# Sheet_1.net
KiCad netlist of a schematic drawn in Altium Designer
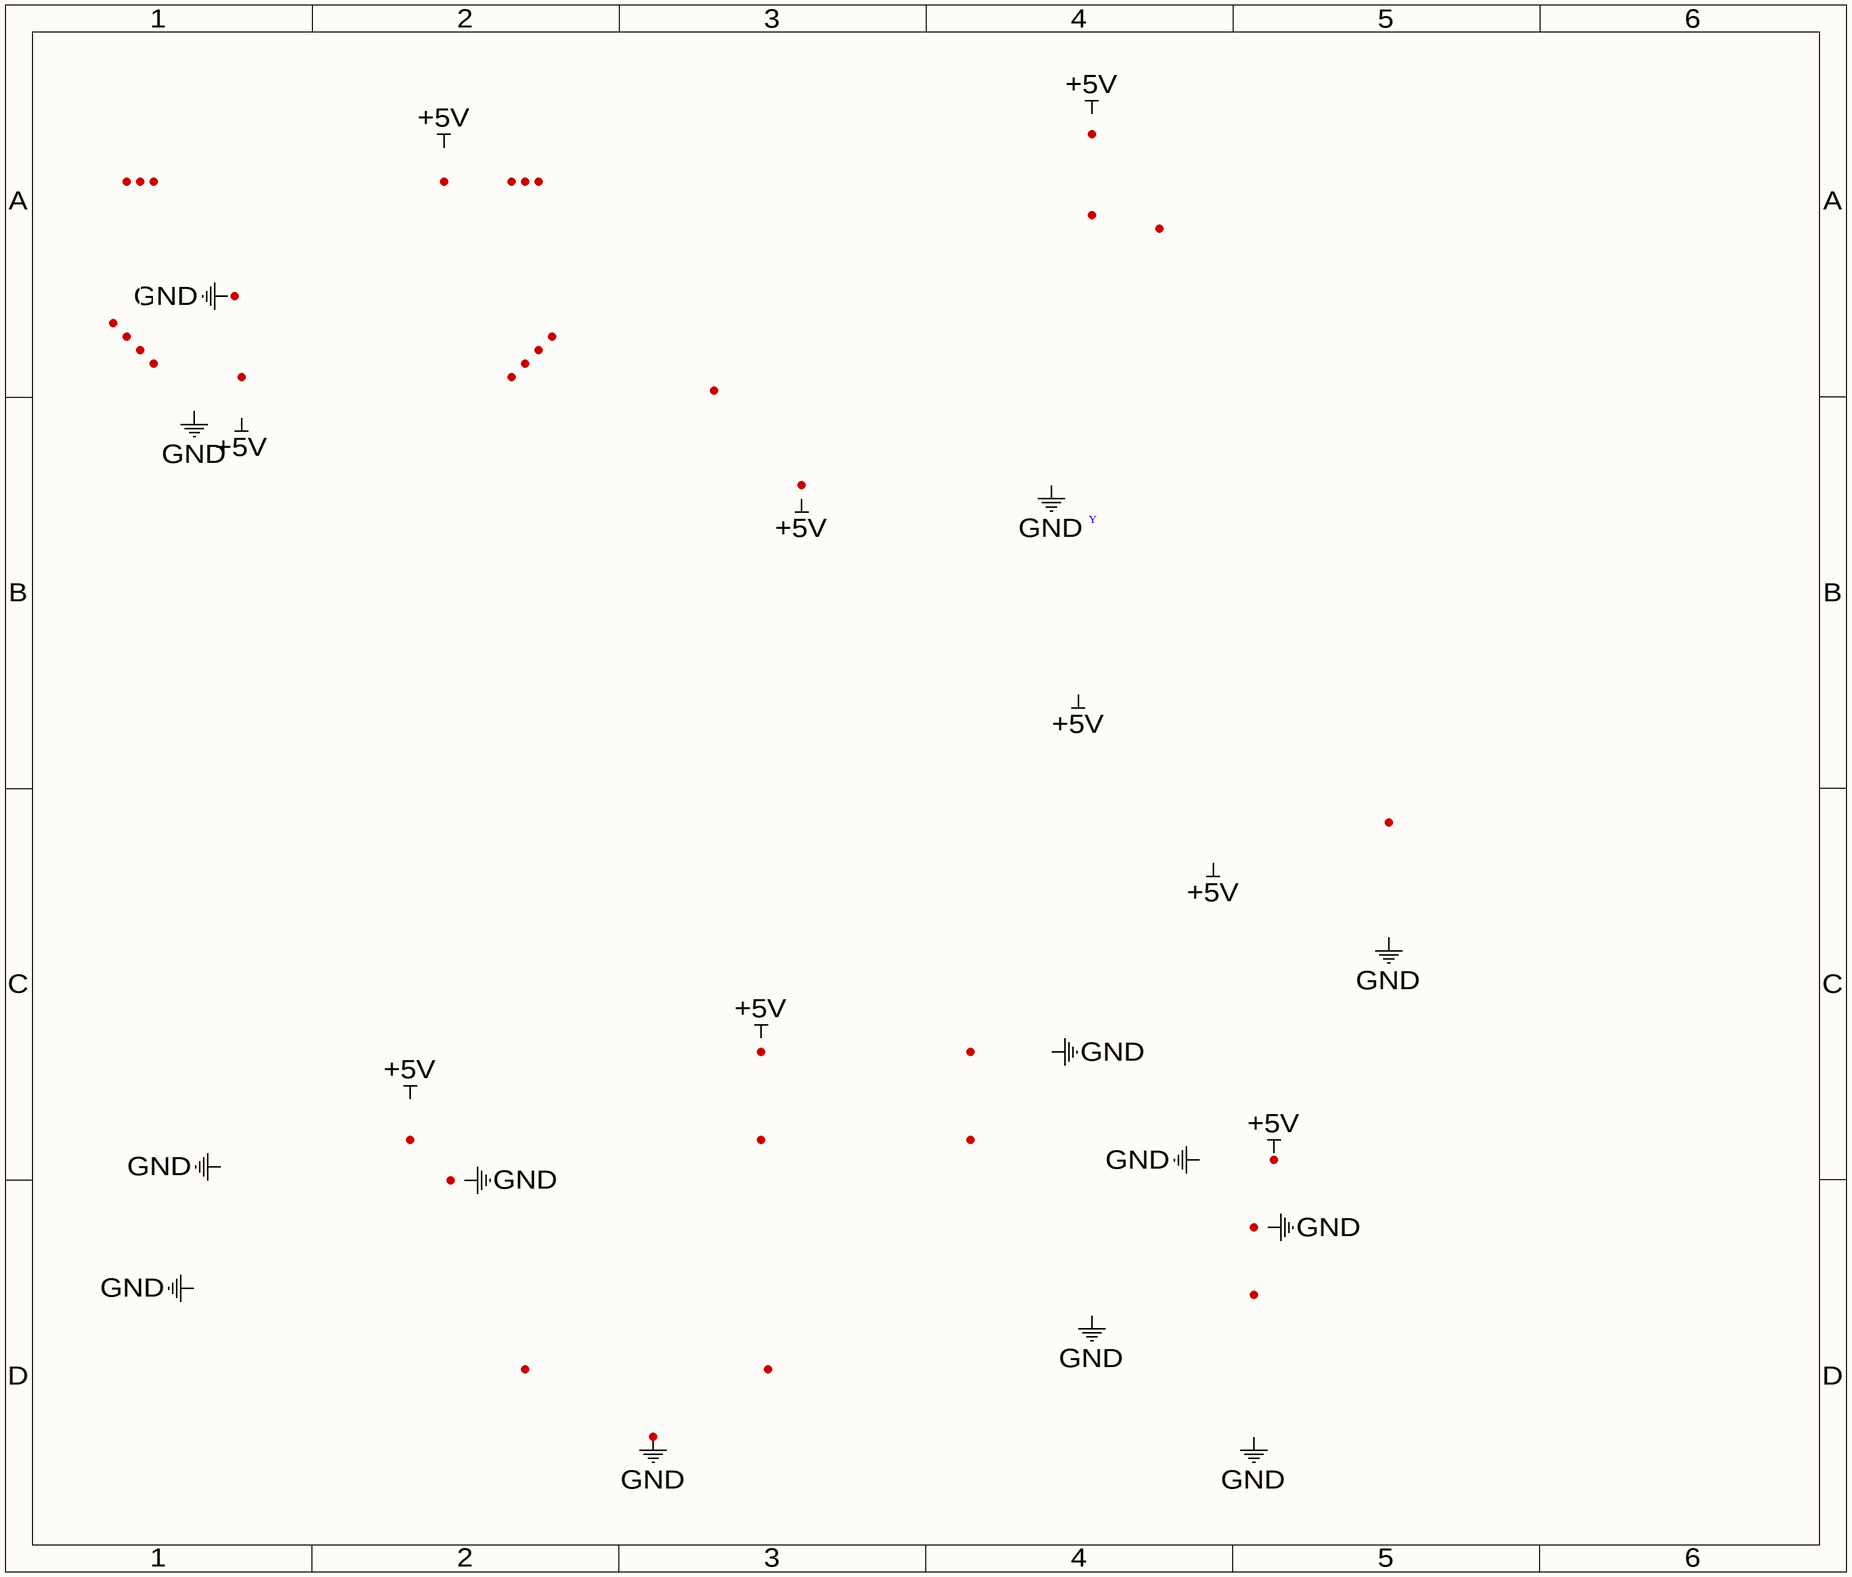
[diagram p0: Sheet_1.schdoc]

(export (version "E")
  (design (tool "Eeschema 10.0.6"))
  (components
    (comp (ref "BOARD1")
      (value "ESP32DEVKITV1")
      (fields (field (name "CONTRIBUTOR") "radio"))
      (libsource (lib "altium-import") (part "root_0_ESP32DEVKITV1_"))
    )
    (comp (ref "C1")
      (value "100nF")
      (fields
        (field (name "BOM_SUPPLIER PART") "C328914")
        (field (name "BOM_MANUFACTURER PART") "FN15X104K160PNG")
        (field (name "CONTRIBUTOR") "LCSC")
      )
      (libsource (lib "altium-import") (part "root_2_100nF_"))
    )
    (comp (ref "C2")
      (value "100nF")
      (fields
        (field (name "BOM_SUPPLIER PART") "C328914")
        (field (name "BOM_MANUFACTURER PART") "FN15X104K160PNG")
        (field (name "CONTRIBUTOR") "LCSC")
      )
      (libsource (lib "altium-import") (part "root_2_100nF_"))
    )
    (comp (ref "C3")
      (value "100nF")
      (fields
        (field (name "BOM_SUPPLIER PART") "C328914")
        (field (name "BOM_MANUFACTURER PART") "FN15X104K160PNG")
        (field (name "CONTRIBUTOR") "LCSC")
      )
      (libsource (lib "altium-import") (part "root_1_100nF_"))
    )
    (comp (ref "C4")
      (value "100nF")
      (fields
        (field (name "BOM_SUPPLIER PART") "C328914")
        (field (name "BOM_MANUFACTURER PART") "FN15X104K160PNG")
        (field (name "CONTRIBUTOR") "LCSC")
      )
      (libsource (lib "altium-import") (part "root_3_100nF_"))
    )
    (comp (ref "C5")
      (value "100nF")
      (fields
        (field (name "BOM_SUPPLIER PART") "C328914")
        (field (name "BOM_MANUFACTURER PART") "FN15X104K160PNG")
        (field (name "CONTRIBUTOR") "LCSC")
      )
      (libsource (lib "altium-import") (part "root_2_100nF_"))
    )
    (comp (ref "C6")
      (value "100nF")
      (fields
        (field (name "BOM_SUPPLIER PART") "C328914")
        (field (name "BOM_MANUFACTURER PART") "FN15X104K160PNG")
        (field (name "CONTRIBUTOR") "LCSC")
      )
      (libsource (lib "altium-import") (part "root_2_100nF_"))
    )
    (comp (ref "D1")
      (value "SS34")
      (fields (field (name "BOM_SUPPLIER PART") "C83961"))
      (libsource (lib "altium-import") (part "root_3_SS34_"))
    )
    (comp (ref "D2")
      (value "SS34")
      (fields (field (name "BOM_SUPPLIER PART") "C83961"))
      (libsource (lib "altium-import") (part "root_3_SS34_"))
    )
    (comp (ref "ERROR")
      (value "17-21SURC/S530-A2/TR8")
      (fields (field (name "BOM_SUPPLIER PART") "C131244") (field (name "CONTRIBUTOR") "LCSC"))
      (libsource (lib "altium-import") (part "root_1_17-21SURC/S530-A2/TR8_"))
    )
    (comp (ref "GC")
      (value "17-21SURC/S530-A2/TR8")
      (fields (field (name "BOM_SUPPLIER PART") "C131244") (field (name "CONTRIBUTOR") "LCSC"))
      (libsource (lib "altium-import") (part "root_1_17-21SURC/S530-A2/TR8_"))
    )
    (comp (ref "GL")
      (value "17-21SURC/S530-A2/TR8")
      (fields (field (name "BOM_SUPPLIER PART") "C131244") (field (name "CONTRIBUTOR") "LCSC"))
      (libsource (lib "altium-import") (part "root_1_17-21SURC/S530-A2/TR8_"))
    )
    (comp (ref "GR")
      (value "17-21SURC/S530-A2/TR8")
      (fields (field (name "BOM_SUPPLIER PART") "C131244") (field (name "CONTRIBUTOR") "LCSC"))
      (libsource (lib "altium-import") (part "root_1_17-21SURC/S530-A2/TR8_"))
    )
    (comp (ref "K1")
      (value "KH-3635-CAJ")
      (fields (field (name "BOM_SUPPLIER PART") "C530670") (field (name "CONTRIBUTOR") "LCSC"))
      (libsource (lib "altium-import") (part "root_0_KH-3635-CAJ_"))
    )
    (comp (ref "K2")
      (value "KH-3635-CAJ")
      (fields (field (name "BOM_SUPPLIER PART") "C530670") (field (name "CONTRIBUTOR") "LCSC"))
      (libsource (lib "altium-import") (part "root_0_KH-3635-CAJ_"))
    )
    (comp (ref "OLED1")
      (value "0.96OLED_4P")
      (fields (field (name "CONTRIBUTOR") "LCEDA_Lib"))
      (libsource (lib "altium-import") (part "root_0_0.96OLED_4P_"))
    )
    (comp (ref "OPEN")
      (value "SK-3296S-01-L1")
      (fields (field (name "BOM_SUPPLIER PART") "C319020") (field (name "CONTRIBUTOR") "LCSC"))
      (libsource (lib "altium-import") (part "root_1_SK-3296S-01-L1_"))
    )
    (comp (ref "POWER")
      (value "17-21SYGC/S530-E3/TR8")
      (fields (field (name "BOM_SUPPLIER PART") "C142303") (field (name "CONTRIBUTOR") "LCSC"))
      (libsource (lib "altium-import") (part "root_1_17-21SYGC/S530-E3/TR8_"))
    )
    (comp (ref "R1")
      (value "510")
      (fields
        (field (name "BOM_MANUFACTURER PART") "0603WAF1002T5E")
        (field (name "BOM_SUPPLIER PART") "C25804")
      )
      (libsource (lib "altium-import") (part "root_1_510_"))
    )
    (comp (ref "R2")
      (value "1k")
      (fields
        (field (name "BOM_MANUFACTURER PART") "0603WAF1002T5E")
        (field (name "BOM_SUPPLIER PART") "C25804")
      )
      (libsource (lib "altium-import") (part "root_1_1k_"))
    )
    (comp (ref "R3")
      (value "1k")
      (fields
        (field (name "BOM_MANUFACTURER PART") "0603WAF1002T5E")
        (field (name "BOM_SUPPLIER PART") "C25804")
      )
      (libsource (lib "altium-import") (part "root_1_1k_"))
    )
    (comp (ref "R4")
      (value "4.7k")
      (fields
        (field (name "BOM_MANUFACTURER PART") "0603WAF1002T5E")
        (field (name "BOM_SUPPLIER PART") "C25804")
      )
      (libsource (lib "altium-import") (part "root_1_4.7k_"))
    )
    (comp (ref "R5")
      (value "4.7k")
      (fields
        (field (name "BOM_MANUFACTURER PART") "0603WAF1002T5E")
        (field (name "BOM_SUPPLIER PART") "C25804")
      )
      (libsource (lib "altium-import") (part "root_1_4.7k_"))
    )
    (comp (ref "RC")
      (value "17-21SURC/S530-A2/TR8")
      (fields (field (name "BOM_SUPPLIER PART") "C131244") (field (name "CONTRIBUTOR") "LCSC"))
      (libsource (lib "altium-import") (part "root_1_17-21SURC/S530-A2/TR8_"))
    )
    (comp (ref "RL")
      (value "17-21SURC/S530-A2/TR8")
      (fields (field (name "BOM_SUPPLIER PART") "C131244") (field (name "CONTRIBUTOR") "LCSC"))
      (libsource (lib "altium-import") (part "root_1_17-21SURC/S530-A2/TR8_"))
    )
    (comp (ref "RN1")
      (value "1k")
      (fields
        (field (name "BOM_MANUFACTURER PART") "YC164-FR-071KL")
        (field (name "BOM_SUPPLIER PART") "C110021")
      )
      (libsource (lib "altium-import") (part "root_0_1k_"))
    )
    (comp (ref "RN2")
      (value "1k")
      (fields
        (field (name "BOM_MANUFACTURER PART") "YC164-FR-071KL")
        (field (name "BOM_SUPPLIER PART") "C110021")
      )
      (libsource (lib "altium-import") (part "root_0_1k_"))
    )
    (comp (ref "RN3")
      (value "1k")
      (fields
        (field (name "BOM_MANUFACTURER PART") "YC164-FR-071KL")
        (field (name "BOM_SUPPLIER PART") "C110021")
      )
      (libsource (lib "altium-import") (part "root_0_1k_"))
    )
    (comp (ref "RN4")
      (value "1k")
      (fields
        (field (name "BOM_MANUFACTURER PART") "YC164-FR-071KL")
        (field (name "BOM_SUPPLIER PART") "C110021")
      )
      (libsource (lib "altium-import") (part "root_0_1k_"))
    )
    (comp (ref "RR")
      (value "17-21SURC/S530-A2/TR8")
      (fields (field (name "BOM_SUPPLIER PART") "C131244") (field (name "CONTRIBUTOR") "LCSC"))
      (libsource (lib "altium-import") (part "root_1_17-21SURC/S530-A2/TR8_"))
    )
    (comp (ref "U1")
      (value "PCF8574T/3,518")
      (fields (field (name "BOM_SUPPLIER PART") "C7605"))
      (libsource (lib "altium-import") (part "root_0_PCF8574T/3,518_"))
    )
    (comp (ref "U2")
      (value "74HC240D,653")
      (fields (field (name "BOM_SUPPLIER PART") "C8094"))
      (libsource (lib "altium-import") (part "root_0_74HC240D,653_"))
    )
    (comp (ref "U3")
      (value "74HC30D,653")
      (fields (field (name "BOM_SUPPLIER PART") "C5631"))
      (libsource (lib "altium-import") (part "root_0_74HC30D,653_"))
    )
    (comp (ref "U4")
      (value "74HC30D,653")
      (fields (field (name "BOM_SUPPLIER PART") "C5631"))
      (libsource (lib "altium-import") (part "root_0_74HC30D,653_"))
    )
    (comp (ref "U5")
      (value "AMS1117-3.3_C347222")
      (fields
        (field (name "BOM_SUPPLIER PART") "C347222")
        (field (name "BOM_MANUFACTURER PART") "AMS1117-3.3")
        (field (name "CONTRIBUTOR") "LCSC")
      )
      (libsource (lib "altium-import") (part "root_0_AMS1117-3.3_C347222_"))
    )
    (comp (ref "U6")
      (value "74HC30D,653")
      (fields (field (name "BOM_SUPPLIER PART") "C5631"))
      (libsource (lib "altium-import") (part "root_0_74HC30D,653_"))
    )
    (comp (ref "U7")
      (value "74HC30D,653")
      (fields (field (name "BOM_SUPPLIER PART") "C5631"))
      (libsource (lib "altium-import") (part "root_0_74HC30D,653_"))
    )
    (comp (ref "U8")
      (value "74HC08D,653")
      (fields (field (name "BOM_SUPPLIER PART") "C5593"))
      (libsource (lib "altium-import") (part "root_0_74HC08D,653_"))
    )
    (comp (ref "USB1")
      (value "KH-TYPE-C-6P")
      (fields (field (name "BOM_SUPPLIER PART") "C709355") (field (name "CONTRIBUTOR") "LCSC"))
      (libsource (lib "altium-import") (part "root_0_KH-TYPE-C-6P_"))
    )
    (comp (ref "YL")
      (value "17-21SURC/S530-A2/TR8")
      (fields (field (name "BOM_SUPPLIER PART") "C131244") (field (name "CONTRIBUTOR") "LCSC"))
      (libsource (lib "altium-import") (part "root_1_17-21SURC/S530-A2/TR8_"))
    )
    (comp (ref "YR")
      (value "17-21SURC/S530-A2/TR8")
      (fields (field (name "BOM_SUPPLIER PART") "C131244") (field (name "CONTRIBUTOR") "LCSC"))
      (libsource (lib "altium-import") (part "root_1_17-21SURC/S530-A2/TR8_"))
    )
  )
  (nets
    (net (code "1") (name "+5V") (class "Default")
      (node (ref "C1") (pin "2") (pinfunction "2_2") (pintype "passive"))
      (node (ref "C2") (pin "1") (pinfunction "1_1") (pintype "passive"))
      (node (ref "C4") (pin "2") (pinfunction "2_2") (pintype "passive"))
      (node (ref "C5") (pin "2") (pinfunction "2_2") (pintype "passive"))
      (node (ref "C6") (pin "1") (pinfunction "1_1") (pintype "passive"))
      (node (ref "D1") (pin "2") (pinfunction "A_2") (pintype "passive"))
      (node (ref "OPEN") (pin "1") (pinfunction "1_1") (pintype "passive"))
      (node (ref "R4") (pin "2") (pinfunction "2_2") (pintype "passive"))
      (node (ref "R5") (pin "2") (pinfunction "2_2") (pintype "passive"))
      (node (ref "RN3") (pin "5") (pinfunction "5_5") (pintype "passive"))
      (node (ref "RN3") (pin "6") (pinfunction "6_6") (pintype "passive"))
      (node (ref "RN3") (pin "7") (pinfunction "7_7") (pintype "passive"))
      (node (ref "RN3") (pin "8") (pinfunction "8_8") (pintype "passive"))
      (node (ref "RN4") (pin "5") (pinfunction "5_5") (pintype "passive"))
      (node (ref "RN4") (pin "6") (pinfunction "6_6") (pintype "passive"))
      (node (ref "RN4") (pin "7") (pinfunction "7_7") (pintype "passive"))
      (node (ref "RN4") (pin "8") (pinfunction "8_8") (pintype "passive"))
      (node (ref "U1") (pin "16") (pinfunction "VDD_16") (pintype "passive"))
      (node (ref "U2") (pin "20") (pinfunction "VCC_20") (pintype "passive"))
      (node (ref "U3") (pin "14") (pinfunction "VCC_14") (pintype "passive"))
      (node (ref "U4") (pin "14") (pinfunction "VCC_14") (pintype "passive"))
      (node (ref "U5") (pin "3") (pinfunction "VIN_3") (pintype "passive"))
      (node (ref "U6") (pin "14") (pinfunction "VCC_14") (pintype "passive"))
      (node (ref "U7") (pin "14") (pinfunction "VCC_14") (pintype "passive"))
      (node (ref "U8") (pin "14") (pinfunction "VCC_14") (pintype "passive"))
    )
    (net (code "2") (name "/+3.3V") (class "Default")
      (node (ref "C3") (pin "1") (pinfunction "1_1") (pintype "passive"))
      (node (ref "OLED1") (pin "2") (pinfunction "2_2") (pintype "passive"))
      (node (ref "R1") (pin "2") (pinfunction "2_2") (pintype "passive"))
      (node (ref "U5") (pin "2") (pinfunction "VOUT(TAB)_2") (pintype "passive"))
      (node (ref "U5") (pin "4") (pinfunction "TAB_4") (pintype "passive"))
    )
    (net (code "3") (name "/A") (class "Default")
      (node (ref "RN1") (pin "8") (pinfunction "8_8") (pintype "passive"))
      (node (ref "RN3") (pin "1") (pinfunction "1_1") (pintype "passive"))
      (node (ref "U1") (pin "4") (pinfunction "P0_4") (pintype "passive"))
      (node (ref "U2") (pin "2") (pinfunction "1A0_2") (pintype "passive"))
      (node (ref "U3") (pin "1") (pinfunction "A_1") (pintype "passive"))
    )
    (net (code "4") (name "/A`") (class "Default")
      (node (ref "U2") (pin "18") (pinfunction "1Y0_18") (pintype "passive"))
      (node (ref "U4") (pin "1") (pinfunction "A_1") (pintype "passive"))
      (node (ref "U6") (pin "1") (pinfunction "A_1") (pintype "passive"))
      (node (ref "U7") (pin "1") (pinfunction "A_1") (pintype "passive"))
    )
    (net (code "5") (name "/B") (class "Default")
      (node (ref "RN1") (pin "7") (pinfunction "7_7") (pintype "passive"))
      (node (ref "RN3") (pin "2") (pinfunction "2_2") (pintype "passive"))
      (node (ref "U1") (pin "5") (pinfunction "P1_5") (pintype "passive"))
      (node (ref "U2") (pin "4") (pinfunction "1A1_4") (pintype "passive"))
      (node (ref "U7") (pin "2") (pinfunction "B_2") (pintype "passive"))
    )
    (net (code "6") (name "/B`") (class "Default")
      (node (ref "U2") (pin "16") (pinfunction "1Y1_16") (pintype "passive"))
      (node (ref "U3") (pin "2") (pinfunction "B_2") (pintype "passive"))
      (node (ref "U4") (pin "2") (pinfunction "B_2") (pintype "passive"))
      (node (ref "U6") (pin "2") (pinfunction "B_2") (pintype "passive"))
    )
    (net (code "7") (name "/C") (class "Default")
      (node (ref "RN1") (pin "6") (pinfunction "6_6") (pintype "passive"))
      (node (ref "RN3") (pin "3") (pinfunction "3_3") (pintype "passive"))
      (node (ref "U1") (pin "6") (pinfunction "P2_6") (pintype "passive"))
      (node (ref "U2") (pin "6") (pinfunction "1A2_6") (pintype "passive"))
      (node (ref "U4") (pin "3") (pinfunction "C_3") (pintype "passive"))
      (node (ref "U6") (pin "3") (pinfunction "C_3") (pintype "passive"))
    )
    (net (code "8") (name "/C`") (class "Default")
      (node (ref "U2") (pin "14") (pinfunction "1Y2_14") (pintype "passive"))
      (node (ref "U3") (pin "3") (pinfunction "C_3") (pintype "passive"))
      (node (ref "U7") (pin "3") (pinfunction "C_3") (pintype "passive"))
    )
    (net (code "9") (name "/D") (class "Default")
      (node (ref "RN1") (pin "5") (pinfunction "5_5") (pintype "passive"))
      (node (ref "RN3") (pin "4") (pinfunction "4_4") (pintype "passive"))
      (node (ref "U1") (pin "7") (pinfunction "P3_7") (pintype "passive"))
      (node (ref "U2") (pin "8") (pinfunction "1A3_8") (pintype "passive"))
      (node (ref "U4") (pin "4") (pinfunction "D_4") (pintype "passive"))
      (node (ref "U6") (pin "4") (pinfunction "D_4") (pintype "passive"))
    )
    (net (code "10") (name "/DC") (class "Default")
      (node (ref "OPEN") (pin "2") (pinfunction "2_2") (pintype "passive"))
      (node (ref "USB1") (pin "A9") (pinfunction "VBUS_A9") (pintype "passive"))
      (node (ref "USB1") (pin "B9") (pinfunction "VBUS_B9") (pintype "passive"))
    )
    (net (code "11") (name "/D`") (class "Default")
      (node (ref "U2") (pin "12") (pinfunction "1Y3_12") (pintype "passive"))
      (node (ref "U3") (pin "4") (pinfunction "D_4") (pintype "passive"))
      (node (ref "U7") (pin "4") (pinfunction "D_4") (pintype "passive"))
    )
    (net (code "12") (name "/E") (class "Default")
      (node (ref "RN2") (pin "8") (pinfunction "8_8") (pintype "passive"))
      (node (ref "RN4") (pin "1") (pinfunction "1_1") (pintype "passive"))
      (node (ref "U1") (pin "9") (pinfunction "P4_9") (pintype "passive"))
      (node (ref "U2") (pin "17") (pinfunction "2A0_17") (pintype "passive"))
      (node (ref "U7") (pin "5") (pinfunction "E_5") (pintype "passive"))
    )
    (net (code "13") (name "/E`") (class "Default")
      (node (ref "U2") (pin "3") (pinfunction "2Y0_3") (pintype "passive"))
      (node (ref "U3") (pin "5") (pinfunction "E_5") (pintype "passive"))
      (node (ref "U4") (pin "5") (pinfunction "E_5") (pintype "passive"))
      (node (ref "U6") (pin "5") (pinfunction "E_5") (pintype "passive"))
    )
    (net (code "14") (name "/F") (class "Default")
      (node (ref "RN2") (pin "7") (pinfunction "7_7") (pintype "passive"))
      (node (ref "RN4") (pin "2") (pinfunction "2_2") (pintype "passive"))
      (node (ref "U1") (pin "10") (pinfunction "P5_10") (pintype "passive"))
      (node (ref "U2") (pin "15") (pinfunction "2A1_15") (pintype "passive"))
      (node (ref "U3") (pin "6") (pinfunction "F_6") (pintype "passive"))
    )
    (net (code "15") (name "/F`") (class "Default")
      (node (ref "U2") (pin "5") (pinfunction "2Y1_5") (pintype "passive"))
      (node (ref "U4") (pin "6") (pinfunction "F_6") (pintype "passive"))
      (node (ref "U6") (pin "6") (pinfunction "F_6") (pintype "passive"))
      (node (ref "U7") (pin "6") (pinfunction "F_6") (pintype "passive"))
    )
    (net (code "16") (name "/G") (class "Default")
      (node (ref "RN2") (pin "6") (pinfunction "6_6") (pintype "passive"))
      (node (ref "RN4") (pin "3") (pinfunction "3_3") (pintype "passive"))
      (node (ref "U1") (pin "11") (pinfunction "P6_11") (pintype "passive"))
      (node (ref "U2") (pin "13") (pinfunction "2A2_13") (pintype "passive"))
      (node (ref "U3") (pin "11") (pinfunction "G_11") (pintype "passive"))
      (node (ref "U4") (pin "11") (pinfunction "G_11") (pintype "passive"))
      (node (ref "U7") (pin "11") (pinfunction "G_11") (pintype "passive"))
    )
    (net (code "17") (name "/G`") (class "Default")
      (node (ref "U2") (pin "7") (pinfunction "2Y2_7") (pintype "passive"))
      (node (ref "U6") (pin "11") (pinfunction "G_11") (pintype "passive"))
    )
    (net (code "18") (name "/H") (class "Default")
      (node (ref "RN2") (pin "5") (pinfunction "5_5") (pintype "passive"))
      (node (ref "RN4") (pin "4") (pinfunction "4_4") (pintype "passive"))
      (node (ref "U1") (pin "12") (pinfunction "P7_12") (pintype "passive"))
      (node (ref "U2") (pin "11") (pinfunction "2A3_11") (pintype "passive"))
      (node (ref "U6") (pin "12") (pinfunction "H_12") (pintype "passive"))
    )
    (net (code "19") (name "/H`") (class "Default")
      (node (ref "U2") (pin "9") (pinfunction "2Y3_9") (pintype "passive"))
      (node (ref "U3") (pin "12") (pinfunction "H_12") (pintype "passive"))
      (node (ref "U4") (pin "12") (pinfunction "H_12") (pintype "passive"))
      (node (ref "U7") (pin "12") (pinfunction "H_12") (pintype "passive"))
    )
    (net (code "20") (name "/K1") (class "Default")
      (node (ref "BOARD1") (pin "D17") (pinfunction "D17_D17") (pintype "passive"))
      (node (ref "K1") (pin "1") (pinfunction "C_1") (pintype "passive"))
    )
    (net (code "21") (name "/K2") (class "Default")
      (node (ref "BOARD1") (pin "D16") (pinfunction "D16_D16") (pintype "passive"))
      (node (ref "K2") (pin "1") (pinfunction "C_1") (pintype "passive"))
    )
    (net (code "22") (name "/SCL") (class "Default")
      (node (ref "BOARD1") (pin "D23") (pinfunction "D23_D23") (pintype "passive"))
      (node (ref "OLED1") (pin "3") (pinfunction "3_3") (pintype "passive"))
      (node (ref "R4") (pin "1") (pinfunction "1_1") (pintype "passive"))
      (node (ref "U1") (pin "14") (pinfunction "SCL_14") (pintype "passive"))
    )
    (net (code "23") (name "/SDA") (class "Default")
      (node (ref "BOARD1") (pin "D22") (pinfunction "D22_D22") (pintype "passive"))
      (node (ref "OLED1") (pin "4") (pinfunction "4_4") (pintype "passive"))
      (node (ref "R5") (pin "1") (pinfunction "1_1") (pintype "passive"))
      (node (ref "U1") (pin "15") (pinfunction "SDA_15") (pintype "passive"))
    )
    (net (code "24") (name "/Y") (class "Default")
      (node (ref "R2") (pin "2") (pinfunction "2_2") (pintype "passive"))
      (node (ref "R3") (pin "1") (pinfunction "1_1") (pintype "passive"))
      (node (ref "U8") (pin "8") (pinfunction "3Y_8") (pintype "passive"))
    )
    (net (code "25") (name "/Y1") (class "Default")
      (node (ref "U3") (pin "8") (pinfunction "Y_8") (pintype "passive"))
      (node (ref "U8") (pin "1") (pinfunction "1A_1") (pintype "passive"))
    )
    (net (code "26") (name "/Y2") (class "Default")
      (node (ref "U4") (pin "8") (pinfunction "Y_8") (pintype "passive"))
      (node (ref "U8") (pin "2") (pinfunction "1B_2") (pintype "passive"))
    )
    (net (code "27") (name "/Y3") (class "Default")
      (node (ref "U6") (pin "8") (pinfunction "Y_8") (pintype "passive"))
      (node (ref "U8") (pin "5") (pinfunction "2B_5") (pintype "passive"))
    )
    (net (code "28") (name "/Y4") (class "Default")
      (node (ref "U7") (pin "8") (pinfunction "Y_8") (pintype "passive"))
      (node (ref "U8") (pin "10") (pinfunction "3B_10") (pintype "passive"))
    )
    (net (code "29") (name "GND") (class "Default")
      (node (ref "BOARD1") (pin "GND") (pinfunction "GND_GND") (pintype "passive"))
      (node (ref "BOARD1") (pin "GND@1") (pinfunction "GND_GND@1") (pintype "passive"))
      (node (ref "C1") (pin "1") (pinfunction "1_1") (pintype "passive"))
      (node (ref "C2") (pin "2") (pinfunction "2_2") (pintype "passive"))
      (node (ref "C3") (pin "2") (pinfunction "2_2") (pintype "passive"))
      (node (ref "C4") (pin "1") (pinfunction "1_1") (pintype "passive"))
      (node (ref "C5") (pin "1") (pinfunction "1_1") (pintype "passive"))
      (node (ref "C6") (pin "2") (pinfunction "2_2") (pintype "passive"))
      (node (ref "ERROR") (pin "1") (pinfunction "K_1") (pintype "passive"))
      (node (ref "GC") (pin "1") (pinfunction "K_1") (pintype "passive"))
      (node (ref "GL") (pin "1") (pinfunction "K_1") (pintype "passive"))
      (node (ref "GR") (pin "1") (pinfunction "K_1") (pintype "passive"))
      (node (ref "K1") (pin "2") (pinfunction "D_2") (pintype "passive"))
      (node (ref "K1") (pin "4") (pinfunction "B_4") (pintype "passive"))
      (node (ref "K2") (pin "2") (pinfunction "D_2") (pintype "passive"))
      (node (ref "K2") (pin "4") (pinfunction "B_4") (pintype "passive"))
      (node (ref "OLED1") (pin "1") (pinfunction "1_1") (pintype "passive"))
      (node (ref "POWER") (pin "1") (pinfunction "K_1") (pintype "passive"))
      (node (ref "RC") (pin "1") (pinfunction "K_1") (pintype "passive"))
      (node (ref "RL") (pin "1") (pinfunction "K_1") (pintype "passive"))
      (node (ref "RR") (pin "1") (pinfunction "K_1") (pintype "passive"))
      (node (ref "U1") (pin "1") (pinfunction "A0_1") (pintype "passive"))
      (node (ref "U1") (pin "2") (pinfunction "A1_2") (pintype "passive"))
      (node (ref "U1") (pin "3") (pinfunction "A2_3") (pintype "passive"))
      (node (ref "U1") (pin "8") (pinfunction "VSS_8") (pintype "passive"))
      (node (ref "U2") (pin "1") (pinfunction "1OE#_1") (pintype "passive"))
      (node (ref "U2") (pin "10") (pinfunction "GND_10") (pintype "passive"))
      (node (ref "U2") (pin "19") (pinfunction "2OE#_19") (pintype "passive"))
      (node (ref "U3") (pin "7") (pinfunction "GND_7") (pintype "passive"))
      (node (ref "U4") (pin "7") (pinfunction "GND_7") (pintype "passive"))
      (node (ref "U5") (pin "1") (pinfunction "ADJ(GND)_1") (pintype "passive"))
      (node (ref "U6") (pin "7") (pinfunction "GND_7") (pintype "passive"))
      (node (ref "U7") (pin "7") (pinfunction "GND_7") (pintype "passive"))
      (node (ref "U8") (pin "12") (pinfunction "4A_12") (pintype "passive"))
      (node (ref "U8") (pin "13") (pinfunction "4B_13") (pintype "passive"))
      (node (ref "U8") (pin "7") (pinfunction "GND_7") (pintype "passive"))
      (node (ref "USB1") (pin "1") (pinfunction "EP_1") (pintype "passive"))
      (node (ref "USB1") (pin "2") (pinfunction "EP_2") (pintype "passive"))
      (node (ref "USB1") (pin "3") (pinfunction "EP_3") (pintype "passive"))
      (node (ref "USB1") (pin "4") (pinfunction "EP_4") (pintype "passive"))
      (node (ref "USB1") (pin "A12") (pinfunction "GND_A12") (pintype "passive"))
      (node (ref "USB1") (pin "B12") (pinfunction "GND_B12") (pintype "passive"))
      (node (ref "YL") (pin "1") (pinfunction "K_1") (pintype "passive"))
      (node (ref "YR") (pin "1") (pinfunction "K_1") (pintype "passive"))
    )
    (net (code "30") (name "Net-(D1-C)") (class "Default")
      (node (ref "BOARD1") (pin "VIN") (pinfunction "VIN_VIN") (pintype "passive"))
      (node (ref "D1") (pin "1") (pinfunction "C_1") (pintype "passive"))
    )
    (net (code "31") (name "Net-(D2-A)") (class "Default")
      (node (ref "D2") (pin "2") (pinfunction "A_2") (pintype "passive"))
      (node (ref "R3") (pin "2") (pinfunction "2_2") (pintype "passive"))
    )
    (net (code "32") (name "Net-(D2-C)") (class "Default")
      (node (ref "BOARD1") (pin "D15") (pinfunction "D15_D15") (pintype "passive"))
      (node (ref "D2") (pin "1") (pinfunction "C_1") (pintype "passive"))
    )
    (net (code "33") (name "Net-(ERROR-A)") (class "Default")
      (node (ref "ERROR") (pin "2") (pinfunction "A_2") (pintype "passive"))
      (node (ref "R2") (pin "1") (pinfunction "1_1") (pintype "passive"))
    )
    (net (code "34") (name "Net-(GC-A)") (class "Default")
      (node (ref "GC") (pin "2") (pinfunction "A_2") (pintype "passive"))
      (node (ref "RN2") (pin "4") (pinfunction "4_4") (pintype "passive"))
    )
    (net (code "35") (name "Net-(GL-A)") (class "Default")
      (node (ref "GL") (pin "2") (pinfunction "A_2") (pintype "passive"))
      (node (ref "RN1") (pin "3") (pinfunction "3_3") (pintype "passive"))
    )
    (net (code "36") (name "Net-(GR-A)") (class "Default")
      (node (ref "GR") (pin "2") (pinfunction "A_2") (pintype "passive"))
      (node (ref "RN2") (pin "2") (pinfunction "2_2") (pintype "passive"))
    )
    (net (code "37") (name "Net-(POWER-A)") (class "Default")
      (node (ref "POWER") (pin "2") (pinfunction "A_2") (pintype "passive"))
      (node (ref "R1") (pin "1") (pinfunction "1_1") (pintype "passive"))
    )
    (net (code "38") (name "Net-(RC-A)") (class "Default")
      (node (ref "RC") (pin "2") (pinfunction "A_2") (pintype "passive"))
      (node (ref "RN2") (pin "3") (pinfunction "3_3") (pintype "passive"))
    )
    (net (code "39") (name "Net-(RL-A)") (class "Default")
      (node (ref "RL") (pin "2") (pinfunction "A_2") (pintype "passive"))
      (node (ref "RN1") (pin "1") (pinfunction "1_1") (pintype "passive"))
    )
    (net (code "40") (name "Net-(RR-A)") (class "Default")
      (node (ref "RN1") (pin "4") (pinfunction "4_4") (pintype "passive"))
      (node (ref "RR") (pin "2") (pinfunction "A_2") (pintype "passive"))
    )
    (net (code "41") (name "Net-(U8-1Y)") (class "Default")
      (node (ref "U8") (pin "3") (pinfunction "1Y_3") (pintype "passive"))
      (node (ref "U8") (pin "4") (pinfunction "2A_4") (pintype "passive"))
    )
    (net (code "42") (name "Net-(U8-2Y)") (class "Default")
      (node (ref "U8") (pin "6") (pinfunction "2Y_6") (pintype "passive"))
      (node (ref "U8") (pin "9") (pinfunction "3A_9") (pintype "passive"))
    )
    (net (code "43") (name "Net-(YL-A)") (class "Default")
      (node (ref "RN1") (pin "2") (pinfunction "2_2") (pintype "passive"))
      (node (ref "YL") (pin "2") (pinfunction "A_2") (pintype "passive"))
    )
    (net (code "44") (name "Net-(YR-A)") (class "Default")
      (node (ref "RN2") (pin "1") (pinfunction "1_1") (pintype "passive"))
      (node (ref "YR") (pin "2") (pinfunction "A_2") (pintype "passive"))
    )
    (net (code "45") (name "unconnected-(BOARD1-Pad3V3)") (class "Default")
      (node (ref "BOARD1") (pin "3V3") (pinfunction "3V3_3V3") (pintype "passive"))
    )
    (net (code "46") (name "unconnected-(BOARD1-PadD1)") (class "Default")
      (node (ref "BOARD1") (pin "D1") (pinfunction "D1_D1") (pintype "passive"))
    )
    (net (code "47") (name "unconnected-(BOARD1-PadD2)") (class "Default")
      (node (ref "BOARD1") (pin "D2") (pinfunction "D2_D2") (pintype "passive"))
    )
    (net (code "48") (name "unconnected-(BOARD1-PadD3)") (class "Default")
      (node (ref "BOARD1") (pin "D3") (pinfunction "D3_D3") (pintype "passive"))
    )
    (net (code "49") (name "unconnected-(BOARD1-PadD4)") (class "Default")
      (node (ref "BOARD1") (pin "D4") (pinfunction "D4_D4") (pintype "passive"))
    )
    (net (code "50") (name "unconnected-(BOARD1-PadD5)") (class "Default")
      (node (ref "BOARD1") (pin "D5") (pinfunction "D5_D5") (pintype "passive"))
    )
    (net (code "51") (name "unconnected-(BOARD1-PadD12)") (class "Default")
      (node (ref "BOARD1") (pin "D12") (pinfunction "D12_D12") (pintype "passive"))
    )
    (net (code "52") (name "unconnected-(BOARD1-PadD13)") (class "Default")
      (node (ref "BOARD1") (pin "D13") (pinfunction "D13_D13") (pintype "passive"))
    )
    (net (code "53") (name "unconnected-(BOARD1-PadD14)") (class "Default")
      (node (ref "BOARD1") (pin "D14") (pinfunction "D14_D14") (pintype "passive"))
    )
    (net (code "54") (name "unconnected-(BOARD1-PadD18)") (class "Default")
      (node (ref "BOARD1") (pin "D18") (pinfunction "D18_D18") (pintype "passive"))
    )
    (net (code "55") (name "unconnected-(BOARD1-PadD19)") (class "Default")
      (node (ref "BOARD1") (pin "D19") (pinfunction "D19_D19") (pintype "passive"))
    )
    (net (code "56") (name "unconnected-(BOARD1-PadD21)") (class "Default")
      (node (ref "BOARD1") (pin "D21") (pinfunction "D21_D21") (pintype "passive"))
    )
    (net (code "57") (name "unconnected-(BOARD1-PadD25)") (class "Default")
      (node (ref "BOARD1") (pin "D25") (pinfunction "D25_D25") (pintype "passive"))
    )
    (net (code "58") (name "unconnected-(BOARD1-PadD26)") (class "Default")
      (node (ref "BOARD1") (pin "D26") (pinfunction "D26_D26") (pintype "passive"))
    )
    (net (code "59") (name "unconnected-(BOARD1-PadD27)") (class "Default")
      (node (ref "BOARD1") (pin "D27") (pinfunction "D27_D27") (pintype "passive"))
    )
    (net (code "60") (name "unconnected-(BOARD1-PadD32)") (class "Default")
      (node (ref "BOARD1") (pin "D32") (pinfunction "D32_D32") (pintype "passive"))
    )
    (net (code "61") (name "unconnected-(BOARD1-PadD33)") (class "Default")
      (node (ref "BOARD1") (pin "D33") (pinfunction "D33_D33") (pintype "passive"))
    )
    (net (code "62") (name "unconnected-(BOARD1-PadD34)") (class "Default")
      (node (ref "BOARD1") (pin "D34") (pinfunction "D34_D34") (pintype "passive"))
    )
    (net (code "63") (name "unconnected-(BOARD1-PadD35)") (class "Default")
      (node (ref "BOARD1") (pin "D35") (pinfunction "D35_D35") (pintype "passive"))
    )
    (net (code "64") (name "unconnected-(BOARD1-PadEN)") (class "Default")
      (node (ref "BOARD1") (pin "EN") (pinfunction "EN_EN") (pintype "passive"))
    )
    (net (code "65") (name "unconnected-(BOARD1-PadVN)") (class "Default")
      (node (ref "BOARD1") (pin "VN") (pinfunction "VN_VN") (pintype "passive"))
    )
    (net (code "66") (name "unconnected-(BOARD1-PadVP)") (class "Default")
      (node (ref "BOARD1") (pin "VP") (pinfunction "VP_VP") (pintype "passive"))
    )
    (net (code "67") (name "unconnected-(K1-A-Pad3)") (class "Default")
      (node (ref "K1") (pin "3") (pinfunction "A_3") (pintype "passive"))
    )
    (net (code "68") (name "unconnected-(K2-A-Pad3)") (class "Default")
      (node (ref "K2") (pin "3") (pinfunction "A_3") (pintype "passive"))
    )
    (net (code "69") (name "unconnected-(OPEN-Pad0)") (class "Default")
      (node (ref "OPEN") (pin "0") (pinfunction "0_0") (pintype "passive"))
    )
    (net (code "70") (name "unconnected-(OPEN-Pad3)") (class "Default")
      (node (ref "OPEN") (pin "3") (pinfunction "3_3") (pintype "passive"))
    )
    (net (code "71") (name "unconnected-(U1-INT#-Pad13)") (class "Default")
      (node (ref "U1") (pin "13") (pinfunction "INT#_13") (pintype "passive"))
    )
    (net (code "72") (name "unconnected-(U3-N.C.-Pad9)") (class "Default")
      (node (ref "U3") (pin "9") (pinfunction "N.C._9") (pintype "passive"))
    )
    (net (code "73") (name "unconnected-(U3-N.C.{slash}2-Pad13)") (class "Default")
      (node (ref "U3") (pin "13") (pinfunction "N.C./2_13") (pintype "passive"))
    )
    (net (code "74") (name "unconnected-(U3-N.C.{slash}3-Pad10)") (class "Default")
      (node (ref "U3") (pin "10") (pinfunction "N.C./3_10") (pintype "passive"))
    )
    (net (code "75") (name "unconnected-(U4-N.C.-Pad9)") (class "Default")
      (node (ref "U4") (pin "9") (pinfunction "N.C._9") (pintype "passive"))
    )
    (net (code "76") (name "unconnected-(U4-N.C.{slash}2-Pad13)") (class "Default")
      (node (ref "U4") (pin "13") (pinfunction "N.C./2_13") (pintype "passive"))
    )
    (net (code "77") (name "unconnected-(U4-N.C.{slash}3-Pad10)") (class "Default")
      (node (ref "U4") (pin "10") (pinfunction "N.C./3_10") (pintype "passive"))
    )
    (net (code "78") (name "unconnected-(U6-N.C.-Pad9)") (class "Default")
      (node (ref "U6") (pin "9") (pinfunction "N.C._9") (pintype "passive"))
    )
    (net (code "79") (name "unconnected-(U6-N.C.{slash}2-Pad13)") (class "Default")
      (node (ref "U6") (pin "13") (pinfunction "N.C./2_13") (pintype "passive"))
    )
    (net (code "80") (name "unconnected-(U6-N.C.{slash}3-Pad10)") (class "Default")
      (node (ref "U6") (pin "10") (pinfunction "N.C./3_10") (pintype "passive"))
    )
    (net (code "81") (name "unconnected-(U7-N.C.-Pad9)") (class "Default")
      (node (ref "U7") (pin "9") (pinfunction "N.C._9") (pintype "passive"))
    )
    (net (code "82") (name "unconnected-(U7-N.C.{slash}2-Pad13)") (class "Default")
      (node (ref "U7") (pin "13") (pinfunction "N.C./2_13") (pintype "passive"))
    )
    (net (code "83") (name "unconnected-(U7-N.C.{slash}3-Pad10)") (class "Default")
      (node (ref "U7") (pin "10") (pinfunction "N.C./3_10") (pintype "passive"))
    )
    (net (code "84") (name "unconnected-(U8-4Y-Pad11)") (class "Default")
      (node (ref "U8") (pin "11") (pinfunction "4Y_11") (pintype "passive"))
    )
    (net (code "85") (name "unconnected-(USB1-CC1-PadA5)") (class "Default")
      (node (ref "USB1") (pin "A5") (pinfunction "CC1_A5") (pintype "passive"))
    )
    (net (code "86") (name "unconnected-(USB1-CC2-PadB5)") (class "Default")
      (node (ref "USB1") (pin "B5") (pinfunction "CC2_B5") (pintype "passive"))
    )
  )
)
